# xambi_1_0.net
KiCad netlist of a schematic drawn in EAGLE
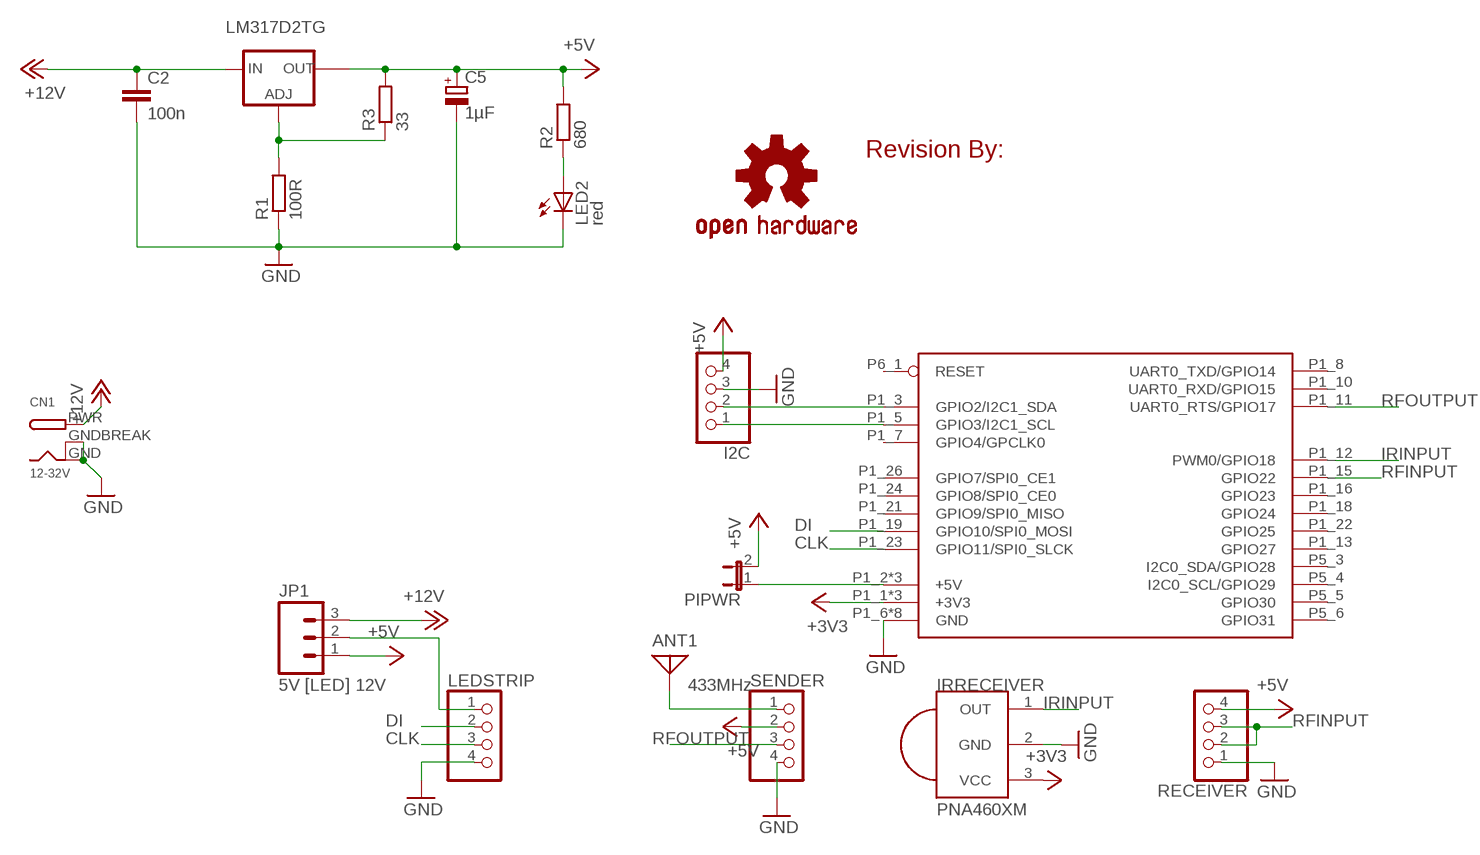
[diagram p0: schematic, sheet 1]

(export (version "E")
  (design (tool "Eeschema 10.0.6"))
  (components
    (comp (ref "ANT1")
      (value "433MHz")
      (footprint "eagle-import:PAD-01")
      (libsource (lib "eagle-import") (part "ANTENNA"))
    )
    (comp (ref "C2")
      (value "100n")
      (footprint "eagle-import:C1206")
      (libsource (lib "eagle-import") (part "C-EUC1206"))
    )
    (comp (ref "C5")
      (value "1µF")
      (footprint "eagle-import:UD-4X5,8_NICHICON")
      (libsource (lib "eagle-import") (part "CPOL-EUUD-4X5,8"))
    )
    (comp (ref "CN1")
      (value "12-32V")
      (footprint "eagle-import:DCJACK_2MM_PTH")
      (libsource (lib "eagle-import") (part "DCBARRELPTH"))
    )
    (comp (ref "I2C")
      (value "PINHD-1X4")
      (footprint "eagle-import:1X04")
      (libsource (lib "eagle-import") (part "PINHD-1X4"))
    )
    (comp (ref "IRRECEIVER")
      (value "PNA460XM")
      (footprint "eagle-import:PNA460XM")
      (libsource (lib "eagle-import") (part "PNA460XM"))
    )
    (comp (ref "JP1")
      (value "5V [LED] 12V")
      (footprint "eagle-import:1X03")
      (libsource (lib "eagle-import") (part "M03PTH"))
    )
    (comp (ref "LED2")
      (value "red")
      (footprint "eagle-import:CHIPLED_1206")
      (libsource (lib "eagle-import") (part "LEDCHIPLED_1206"))
    )
    (comp (ref "LEDSTRIP")
      (value "PINHD-1X4")
      (footprint "eagle-import:1X04")
      (libsource (lib "eagle-import") (part "PINHD-1X4"))
    )
    (comp (ref "LM317D2TG")
      (value "LM1084IS")
      (footprint "eagle-import:TO263")
      (libsource (lib "eagle-import") (part "LM1084IS"))
    )
    (comp (ref "LOGO1")
      (value "OSHW-LOGOS")
      (footprint "eagle-import:OSHW-LOGO-S")
      (libsource (lib "eagle-import") (part "OSHW-LOGOS"))
    )
    (comp (ref "PIPWR")
      (value "JP1E")
      (footprint "eagle-import:JP1")
      (libsource (lib "eagle-import") (part "JP1E"))
    )
    (comp (ref "R1")
      (value "100R")
      (footprint "eagle-import:R1206")
      (libsource (lib "eagle-import") (part "R-EU_R1206"))
    )
    (comp (ref "R2")
      (value "680")
      (footprint "eagle-import:R1206")
      (libsource (lib "eagle-import") (part "R-EU_R1206"))
    )
    (comp (ref "R3")
      (value "33")
      (footprint "eagle-import:R1206")
      (libsource (lib "eagle-import") (part "R-EU_R1206"))
    )
    (comp (ref "RECEIVER")
      (value "PINHD-1X4")
      (footprint "eagle-import:1X04")
      (libsource (lib "eagle-import") (part "PINHD-1X4"))
    )
    (comp (ref "SENDER")
      (value "PINHD-1X4")
      (footprint "eagle-import:1X04")
      (libsource (lib "eagle-import") (part "PINHD-1X4"))
    )
    (comp (ref "U$2")
      (value "REVISION")
      (footprint "eagle-import:REVISION")
      (libsource (lib "eagle-import") (part "REVISION"))
    )
    (comp (ref "XAMBI_SHIELD_1.0")
      (value "XPIX Dev. / 2014")
      (footprint "eagle-import:RPI-B-V2")
      (libsource (lib "eagle-import") (part "RPI-B-V2NO_SHIELD"))
    )
  )
  (nets
    (net (code "1") (name "+3V3") (class "Default")
      (node (ref "IRRECEIVER") (pin "3") (pinfunction "VCC_3") (pintype "power_in"))
      (node (ref "XAMBI_SHIELD_1.0") (pin "P1_1") (pinfunction "+3V3_P1_1") (pintype "power_in"))
      (node (ref "XAMBI_SHIELD_1.0") (pin "P1_17") (pinfunction "+3V3_P1_17") (pintype "power_in"))
      (node (ref "XAMBI_SHIELD_1.0") (pin "P5_2") (pinfunction "+3V3_P5_2") (pintype "power_in"))
    )
    (net (code "2") (name "+5V") (class "Default")
      (node (ref "C5") (pin "+") (pinfunction "+_+") (pintype "passive"))
      (node (ref "I2C") (pin "4") (pinfunction "4_4") (pintype "passive"))
      (node (ref "JP1") (pin "1") (pinfunction "1_1") (pintype "passive"))
      (node (ref "LM317D2TG") (pin "2") (pinfunction "OUT_2") (pintype "passive"))
      (node (ref "PIPWR") (pin "2") (pinfunction "2_2") (pintype "passive"))
      (node (ref "R2") (pin "2") (pinfunction "2_2") (pintype "passive"))
      (node (ref "R3") (pin "2") (pinfunction "2_2") (pintype "passive"))
      (node (ref "RECEIVER") (pin "4") (pinfunction "4_4") (pintype "passive"))
      (node (ref "SENDER") (pin "2") (pinfunction "2_2") (pintype "passive"))
    )
    (net (code "3") (name "+12V") (class "Default")
      (node (ref "C2") (pin "1") (pinfunction "1_1") (pintype "passive"))
      (node (ref "CN1") (pin "PWR") (pinfunction "PWR_PWR") (pintype "power_in"))
      (node (ref "JP1") (pin "3") (pinfunction "3_3") (pintype "passive"))
      (node (ref "LM317D2TG") (pin "3") (pinfunction "IN_3") (pintype "input"))
    )
    (net (code "4") (name "/CLK") (class "Default")
      (node (ref "LEDSTRIP") (pin "3") (pinfunction "3_3") (pintype "passive"))
      (node (ref "XAMBI_SHIELD_1.0") (pin "P1_23") (pinfunction "GPIO11/SPI0_SLCK_P1_23") (pintype "bidirectional"))
    )
    (net (code "5") (name "/DI") (class "Default")
      (node (ref "LEDSTRIP") (pin "2") (pinfunction "2_2") (pintype "passive"))
      (node (ref "XAMBI_SHIELD_1.0") (pin "P1_19") (pinfunction "GPIO10/SPI0_MOSI_P1_19") (pintype "bidirectional"))
    )
    (net (code "6") (name "/GPIO30") (class "Default")
      (node (ref "XAMBI_SHIELD_1.0") (pin "P5_5") (pinfunction "GPIO30_P5_5") (pintype "power_in"))
    )
    (net (code "7") (name "/GPIO31") (class "Default")
      (node (ref "XAMBI_SHIELD_1.0") (pin "P5_6") (pinfunction "GPIO31_P5_6") (pintype "power_in"))
    )
    (net (code "8") (name "/I2C0_SCL{slash}GPIO29") (class "Default")
      (node (ref "XAMBI_SHIELD_1.0") (pin "P5_4") (pinfunction "I2C0_SCL/GPIO29_P5_4") (pintype "power_in"))
    )
    (net (code "9") (name "/I2C0_SDA{slash}GPIO28") (class "Default")
      (node (ref "XAMBI_SHIELD_1.0") (pin "P5_3") (pinfunction "I2C0_SDA/GPIO28_P5_3") (pintype "power_in"))
    )
    (net (code "10") (name "/IRINPUT") (class "Default")
      (node (ref "IRRECEIVER") (pin "1") (pinfunction "OUT_1") (pintype "output"))
      (node (ref "XAMBI_SHIELD_1.0") (pin "P1_12") (pinfunction "PWM0/GPIO18_P1_12") (pintype "bidirectional"))
    )
    (net (code "11") (name "/RESET") (class "Default")
      (node (ref "XAMBI_SHIELD_1.0") (pin "P6_1") (pinfunction "RESET_P6_1") (pintype "power_in"))
    )
    (net (code "12") (name "/RFINPUT") (class "Default")
      (node (ref "RECEIVER") (pin "2") (pinfunction "2_2") (pintype "passive"))
      (node (ref "RECEIVER") (pin "3") (pinfunction "3_3") (pintype "passive"))
      (node (ref "XAMBI_SHIELD_1.0") (pin "P1_15") (pinfunction "GPIO22_P1_15") (pintype "bidirectional"))
    )
    (net (code "13") (name "/RFOUTPUT") (class "Default")
      (node (ref "SENDER") (pin "3") (pinfunction "3_3") (pintype "passive"))
      (node (ref "XAMBI_SHIELD_1.0") (pin "P1_11") (pinfunction "UART0_RTS/GPIO17_P1_11") (pintype "bidirectional"))
    )
    (net (code "14") (name "GND") (class "Default")
      (node (ref "C2") (pin "2") (pinfunction "2_2") (pintype "passive"))
      (node (ref "C5") (pin "-") (pinfunction "-_-") (pintype "passive"))
      (node (ref "CN1") (pin "GND") (pinfunction "GND_GND") (pintype "power_in"))
      (node (ref "CN1") (pin "GNDBREAK") (pinfunction "GNDBREAK_GNDBREAK") (pintype "power_in"))
      (node (ref "I2C") (pin "3") (pinfunction "3_3") (pintype "passive"))
      (node (ref "IRRECEIVER") (pin "2") (pinfunction "GND_2") (pintype "power_in"))
      (node (ref "LED2") (pin "C") (pinfunction "C_C") (pintype "passive"))
      (node (ref "LEDSTRIP") (pin "4") (pinfunction "4_4") (pintype "passive"))
      (node (ref "R1") (pin "1") (pinfunction "1_1") (pintype "passive"))
      (node (ref "RECEIVER") (pin "1") (pinfunction "1_1") (pintype "passive"))
      (node (ref "SENDER") (pin "4") (pinfunction "4_4") (pintype "passive"))
      (node (ref "XAMBI_SHIELD_1.0") (pin "P1_14") (pinfunction "GND_P1_14") (pintype "power_in"))
      (node (ref "XAMBI_SHIELD_1.0") (pin "P1_20") (pinfunction "GND_P1_20") (pintype "power_in"))
      (node (ref "XAMBI_SHIELD_1.0") (pin "P1_25") (pinfunction "GND_P1_25") (pintype "power_in"))
      (node (ref "XAMBI_SHIELD_1.0") (pin "P1_6") (pinfunction "GND_P1_6") (pintype "power_in"))
      (node (ref "XAMBI_SHIELD_1.0") (pin "P1_9") (pinfunction "GND_P1_9") (pintype "power_in"))
      (node (ref "XAMBI_SHIELD_1.0") (pin "P5_7") (pinfunction "GND_P5_7") (pintype "power_in"))
      (node (ref "XAMBI_SHIELD_1.0") (pin "P5_8") (pinfunction "GND_P5_8") (pintype "power_in"))
      (node (ref "XAMBI_SHIELD_1.0") (pin "P6_2") (pinfunction "GND_P6_2") (pintype "power_in"))
    )
    (net (code "15") (name "Net-(ANT1-Pad1)") (class "Default")
      (node (ref "ANT1") (pin "1") (pinfunction "1_1") (pintype "output"))
      (node (ref "SENDER") (pin "1") (pinfunction "1_1") (pintype "passive"))
    )
    (net (code "16") (name "Net-(JP1-Pad2)") (class "Default")
      (node (ref "JP1") (pin "2") (pinfunction "2_2") (pintype "passive"))
      (node (ref "LEDSTRIP") (pin "1") (pinfunction "1_1") (pintype "passive"))
    )
    (net (code "17") (name "Net-(LED2-PadA)") (class "Default")
      (node (ref "LED2") (pin "A") (pinfunction "A_A") (pintype "passive"))
      (node (ref "R2") (pin "1") (pinfunction "1_1") (pintype "passive"))
    )
    (net (code "18") (name "Net-(LM317D2TG-ADJ)") (class "Default")
      (node (ref "LM317D2TG") (pin "1") (pinfunction "ADJ_1") (pintype "input"))
      (node (ref "R1") (pin "2") (pinfunction "2_2") (pintype "passive"))
      (node (ref "R3") (pin "1") (pinfunction "1_1") (pintype "passive"))
    )
    (net (code "19") (name "Net-(PIPWR-Pad1)") (class "Default")
      (node (ref "PIPWR") (pin "1") (pinfunction "1_1") (pintype "passive"))
      (node (ref "XAMBI_SHIELD_1.0") (pin "P1_2") (pinfunction "+5V_P1_2") (pintype "power_in"))
      (node (ref "XAMBI_SHIELD_1.0") (pin "P1_4") (pinfunction "+5V_P1_4") (pintype "power_in"))
      (node (ref "XAMBI_SHIELD_1.0") (pin "P5_1") (pinfunction "+5V_P5_1") (pintype "power_in"))
    )
    (net (code "20") (name "Net-(XAMBI_SHIELD_1.0-GPIO2{slash}I2C1_SDA)") (class "Default")
      (node (ref "I2C") (pin "2") (pinfunction "2_2") (pintype "passive"))
      (node (ref "XAMBI_SHIELD_1.0") (pin "P1_3") (pinfunction "GPIO2/I2C1_SDA_P1_3") (pintype "bidirectional"))
    )
    (net (code "21") (name "Net-(XAMBI_SHIELD_1.0-GPIO3{slash}I2C1_SCL)") (class "Default")
      (node (ref "I2C") (pin "1") (pinfunction "1_1") (pintype "passive"))
      (node (ref "XAMBI_SHIELD_1.0") (pin "P1_5") (pinfunction "GPIO3/I2C1_SCL_P1_5") (pintype "bidirectional"))
    )
    (net (code "22") (name "unconnected-(LM317D2TG-OUT4-Pad4)") (class "Default")
      (node (ref "LM317D2TG") (pin "4") (pinfunction "OUT4_4") (pintype "passive"))
    )
    (net (code "23") (name "unconnected-(XAMBI_SHIELD_1.0-GPIO4{slash}GPCLK0-PadP1_7)") (class "Default")
      (node (ref "XAMBI_SHIELD_1.0") (pin "P1_7") (pinfunction "GPIO4/GPCLK0_P1_7") (pintype "bidirectional"))
    )
    (net (code "24") (name "unconnected-(XAMBI_SHIELD_1.0-GPIO7{slash}SPI0_CE1-PadP1_26)") (class "Default")
      (node (ref "XAMBI_SHIELD_1.0") (pin "P1_26") (pinfunction "GPIO7/SPI0_CE1_P1_26") (pintype "bidirectional"))
    )
    (net (code "25") (name "unconnected-(XAMBI_SHIELD_1.0-GPIO8{slash}SPI0_CE0-PadP1_24)") (class "Default")
      (node (ref "XAMBI_SHIELD_1.0") (pin "P1_24") (pinfunction "GPIO8/SPI0_CE0_P1_24") (pintype "bidirectional"))
    )
    (net (code "26") (name "unconnected-(XAMBI_SHIELD_1.0-GPIO9{slash}SPI0_MISO-PadP1_21)") (class "Default")
      (node (ref "XAMBI_SHIELD_1.0") (pin "P1_21") (pinfunction "GPIO9/SPI0_MISO_P1_21") (pintype "bidirectional"))
    )
    (net (code "27") (name "unconnected-(XAMBI_SHIELD_1.0-GPIO23-PadP1_16)") (class "Default")
      (node (ref "XAMBI_SHIELD_1.0") (pin "P1_16") (pinfunction "GPIO23_P1_16") (pintype "bidirectional"))
    )
    (net (code "28") (name "unconnected-(XAMBI_SHIELD_1.0-GPIO24-PadP1_18)") (class "Default")
      (node (ref "XAMBI_SHIELD_1.0") (pin "P1_18") (pinfunction "GPIO24_P1_18") (pintype "bidirectional"))
    )
    (net (code "29") (name "unconnected-(XAMBI_SHIELD_1.0-GPIO25-PadP1_22)") (class "Default")
      (node (ref "XAMBI_SHIELD_1.0") (pin "P1_22") (pinfunction "GPIO25_P1_22") (pintype "bidirectional"))
    )
    (net (code "30") (name "unconnected-(XAMBI_SHIELD_1.0-GPIO27-PadP1_13)") (class "Default")
      (node (ref "XAMBI_SHIELD_1.0") (pin "P1_13") (pinfunction "GPIO27_P1_13") (pintype "bidirectional"))
    )
    (net (code "31") (name "unconnected-(XAMBI_SHIELD_1.0-UART0_RXD{slash}GPIO15-PadP1_10)") (class "Default")
      (node (ref "XAMBI_SHIELD_1.0") (pin "P1_10") (pinfunction "UART0_RXD/GPIO15_P1_10") (pintype "bidirectional"))
    )
    (net (code "32") (name "unconnected-(XAMBI_SHIELD_1.0-UART0_TXD{slash}GPIO14-PadP1_8)") (class "Default")
      (node (ref "XAMBI_SHIELD_1.0") (pin "P1_8") (pinfunction "UART0_TXD/GPIO14_P1_8") (pintype "bidirectional"))
    )
  )
)
